# SCH_ECE198-02.net
KiCad netlist of a schematic drawn in EasyEDA
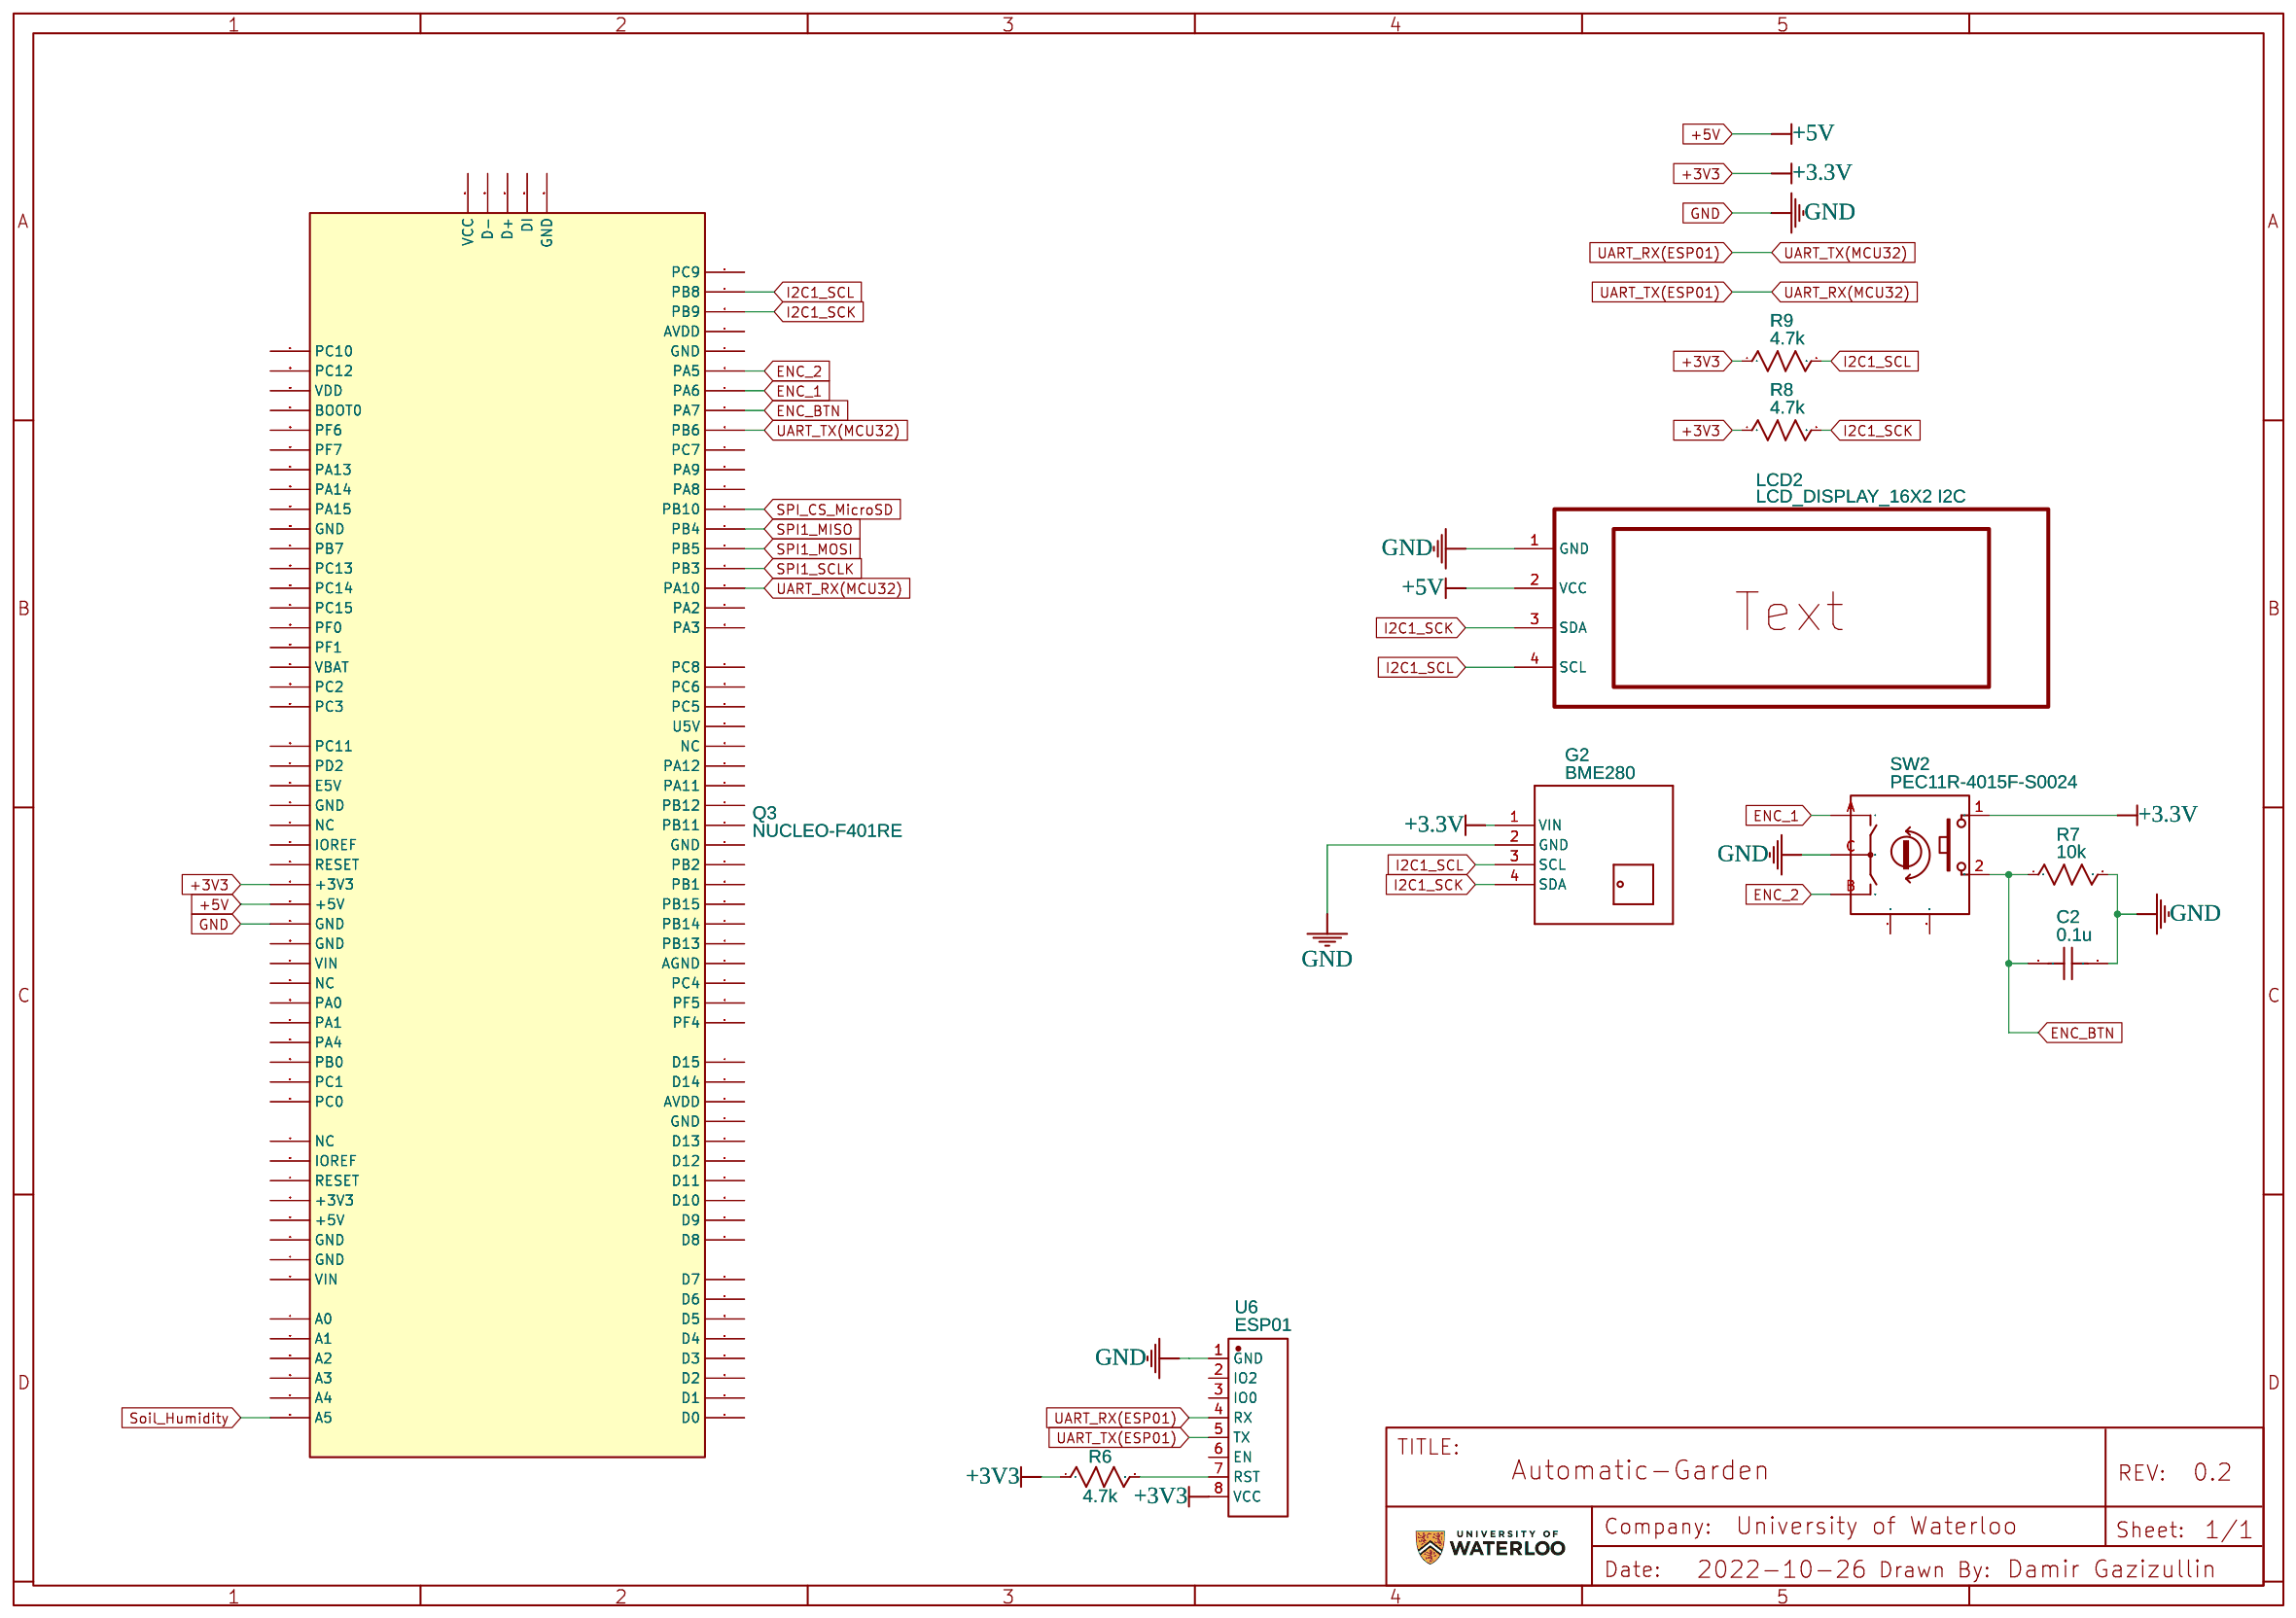
[diagram p0: schematic sheet]

(export (version "E")
  (design (tool "Eeschema 10.0.6"))
  (components
    (comp (ref "C2") (value "0.1u") (libsource (lib "") (part "C_0603_US")))
    (comp (ref "G2") (value "BME280") (libsource (lib "") (part "TEMP-HUM-PRES-BME280")))
    (comp (ref "LCD2") (value "LCD_DISPLAY_16X2 I2C") (libsource (lib "") (part "LCD_DISPLAY_16X2 I2C")))
    (comp (ref "Q3") (value "NUCLEO-F401RE") (libsource (lib "") (part "NUCLEO-F401RE")))
    (comp (ref "R6") (value "4.7k") (libsource (lib "") (part "R_AXIAL-0.5_US")))
    (comp (ref "R7") (value "10k") (libsource (lib "") (part "R_AXIAL-0.5_US")))
    (comp (ref "R8") (value "4.7k") (libsource (lib "") (part "R_0603_US")))
    (comp (ref "R9") (value "4.7k") (libsource (lib "") (part "R_0603_US")))
    (comp (ref "SW2")
      (value "PEC11R-4015F-S0024")
      (fields (field (name "BOM_Supplier Part") "C143789"))
      (libsource (lib "") (part "PEC11R-4015F-S0024"))
    )
    (comp (ref "U6") (value "ESP01") (libsource (lib "") (part "ESP01")))
  )
  (nets
    (net (code "1") (name "+3V3") (class "Default")
      (node (ref "G2") (pin "1") (pinfunction "VIN_1") (pintype "bidirectional"))
      (node (ref "Q3") (pin "91") (pinfunction "+3V3_91") (pintype "unspecified"))
      (node (ref "R6") (pin "1") (pinfunction "1_1") (pintype "unspecified"))
      (node (ref "R8") (pin "1") (pinfunction "1_1") (pintype "unspecified"))
      (node (ref "R9") (pin "1") (pinfunction "1_1") (pintype "unspecified"))
      (node (ref "SW2") (pin "1") (pinfunction "1_1") (pintype "unspecified"))
      (node (ref "U6") (pin "8") (pinfunction "VCC_8") (pintype "unspecified"))
    )
    (net (code "2") (name "+5V") (class "Default")
      (node (ref "LCD2") (pin "2") (pinfunction "VCC_2") (pintype "passive"))
      (node (ref "Q3") (pin "90") (pinfunction "+5V_90") (pintype "unspecified"))
    )
    (net (code "3") (name "ENC_1") (class "Default")
      (node (ref "Q3") (pin "14") (pinfunction "PA6_14") (pintype "bidirectional"))
      (node (ref "SW2") (pin "A") (pinfunction "A_A") (pintype "unspecified"))
    )
    (net (code "4") (name "ENC_2") (class "Default")
      (node (ref "Q3") (pin "13") (pinfunction "PA5_13") (pintype "bidirectional"))
      (node (ref "SW2") (pin "B") (pinfunction "B_B") (pintype "unspecified"))
    )
    (net (code "5") (name "ENC_BTN") (class "Default")
      (node (ref "C2") (pin "1") (pinfunction "1_1") (pintype "unspecified"))
      (node (ref "Q3") (pin "15") (pinfunction "PA7_15") (pintype "bidirectional"))
      (node (ref "R7") (pin "1") (pinfunction "1_1") (pintype "unspecified"))
      (node (ref "SW2") (pin "2") (pinfunction "2_2") (pintype "unspecified"))
    )
    (net (code "6") (name "GND") (class "Default")
      (node (ref "C2") (pin "2") (pinfunction "2_2") (pintype "unspecified"))
      (node (ref "G2") (pin "2") (pinfunction "GND_2") (pintype "bidirectional"))
      (node (ref "LCD2") (pin "1") (pinfunction "GND_1") (pintype "passive"))
      (node (ref "Q3") (pin "89") (pinfunction "GND_89") (pintype "unspecified"))
      (node (ref "R7") (pin "2") (pinfunction "2_2") (pintype "unspecified"))
      (node (ref "SW2") (pin "C") (pinfunction "C_C") (pintype "unspecified"))
      (node (ref "U6") (pin "1") (pinfunction "GND_1") (pintype "unspecified"))
    )
    (net (code "7") (name "I2C1_SCK") (class "Default")
      (node (ref "G2") (pin "4") (pinfunction "SDA_4") (pintype "bidirectional"))
      (node (ref "LCD2") (pin "3") (pinfunction "SDA_3") (pintype "passive"))
      (node (ref "Q3") (pin "10") (pinfunction "PB9_10") (pintype "bidirectional"))
      (node (ref "R8") (pin "2") (pinfunction "2_2") (pintype "unspecified"))
    )
    (net (code "8") (name "I2C1_SCL") (class "Default")
      (node (ref "G2") (pin "3") (pinfunction "SCL_3") (pintype "bidirectional"))
      (node (ref "LCD2") (pin "4") (pinfunction "SCL_4") (pintype "passive"))
      (node (ref "Q3") (pin "9") (pinfunction "PB8_9") (pintype "bidirectional"))
      (node (ref "R9") (pin "2") (pinfunction "2_2") (pintype "unspecified"))
    )
    (net (code "9") (name "Net-(U6-RST)") (class "Default")
      (node (ref "R6") (pin "2") (pinfunction "2_2") (pintype "unspecified"))
      (node (ref "U6") (pin "7") (pinfunction "RST_7") (pintype "unspecified"))
    )
    (net (code "10") (name "SPI1_MISO") (class "Default")
      (node (ref "Q3") (pin "21") (pinfunction "PB4_21") (pintype "bidirectional"))
    )
    (net (code "11") (name "SPI1_MOSI") (class "Default")
      (node (ref "Q3") (pin "22") (pinfunction "PB5_22") (pintype "bidirectional"))
    )
    (net (code "12") (name "SPI1_SCLK") (class "Default")
      (node (ref "Q3") (pin "23") (pinfunction "PB3_23") (pintype "bidirectional"))
    )
    (net (code "13") (name "SPI_CS_MicroSD") (class "Default")
      (node (ref "Q3") (pin "20") (pinfunction "PB10_20") (pintype "bidirectional"))
    )
    (net (code "14") (name "Soil_Humidity") (class "Default")
      (node (ref "Q3") (pin "66") (pinfunction "A5_66") (pintype "unspecified"))
    )
    (net (code "15") (name "UART_RX(ESP01)") (class "Default")
      (node (ref "Q3") (pin "16") (pinfunction "PB6_16") (pintype "bidirectional"))
      (node (ref "U6") (pin "4") (pinfunction "RX_4") (pintype "unspecified"))
    )
    (net (code "16") (name "UART_RX(MCU32)") (class "Default")
      (node (ref "Q3") (pin "24") (pinfunction "PA10_24") (pintype "bidirectional"))
      (node (ref "U6") (pin "5") (pinfunction "TX_5") (pintype "unspecified"))
    )
    (net (code "17") (name "unconnected-(Q3-+3V3-Pad76)") (class "Default")
      (node (ref "Q3") (pin "76") (pinfunction "+3V3_76") (pintype "unspecified"))
    )
    (net (code "18") (name "unconnected-(Q3-+5V-Pad75)") (class "Default")
      (node (ref "Q3") (pin "75") (pinfunction "+5V_75") (pintype "unspecified"))
    )
    (net (code "19") (name "unconnected-(Q3-A0-Pad71)") (class "Default")
      (node (ref "Q3") (pin "71") (pinfunction "A0_71") (pintype "unspecified"))
    )
    (net (code "20") (name "unconnected-(Q3-A1-Pad70)") (class "Default")
      (node (ref "Q3") (pin "70") (pinfunction "A1_70") (pintype "unspecified"))
    )
    (net (code "21") (name "unconnected-(Q3-A2-Pad69)") (class "Default")
      (node (ref "Q3") (pin "69") (pinfunction "A2_69") (pintype "unspecified"))
    )
    (net (code "22") (name "unconnected-(Q3-A3-Pad68)") (class "Default")
      (node (ref "Q3") (pin "68") (pinfunction "A3_68") (pintype "unspecified"))
    )
    (net (code "23") (name "unconnected-(Q3-A4-Pad67)") (class "Default")
      (node (ref "Q3") (pin "67") (pinfunction "A4_67") (pintype "unspecified"))
    )
    (net (code "24") (name "unconnected-(Q3-AGND-Pad43)") (class "Default")
      (node (ref "Q3") (pin "43") (pinfunction "AGND_43") (pintype "unspecified"))
    )
    (net (code "25") (name "unconnected-(Q3-AVDD-Pad11)") (class "Default")
      (node (ref "Q3") (pin "11") (pinfunction "AVDD_11") (pintype "bidirectional"))
    )
    (net (code "26") (name "unconnected-(Q3-AVDD-Pad49)") (class "Default")
      (node (ref "Q3") (pin "49") (pinfunction "AVDD_49") (pintype "unspecified"))
    )
    (net (code "27") (name "unconnected-(Q3-BOOT0-Pad114)") (class "Default")
      (node (ref "Q3") (pin "114") (pinfunction "BOOT0_114") (pintype "unspecified"))
    )
    (net (code "28") (name "unconnected-(Q3-D+-Pad118)") (class "Default")
      (node (ref "Q3") (pin "118") (pinfunction "D+_118") (pintype "unspecified"))
    )
    (net (code "29") (name "unconnected-(Q3-D--Pad118)") (class "Default")
      (node (ref "Q3") (pin "118") (pinfunction "D-_118") (pintype "unspecified"))
    )
    (net (code "30") (name "unconnected-(Q3-D0-Pad65)") (class "Default")
      (node (ref "Q3") (pin "65") (pinfunction "D0_65") (pintype "unspecified"))
    )
    (net (code "31") (name "unconnected-(Q3-D1-Pad64)") (class "Default")
      (node (ref "Q3") (pin "64") (pinfunction "D1_64") (pintype "unspecified"))
    )
    (net (code "32") (name "unconnected-(Q3-D2-Pad63)") (class "Default")
      (node (ref "Q3") (pin "63") (pinfunction "D2_63") (pintype "unspecified"))
    )
    (net (code "33") (name "unconnected-(Q3-D3-Pad62)") (class "Default")
      (node (ref "Q3") (pin "62") (pinfunction "D3_62") (pintype "unspecified"))
    )
    (net (code "34") (name "unconnected-(Q3-D4-Pad61)") (class "Default")
      (node (ref "Q3") (pin "61") (pinfunction "D4_61") (pintype "unspecified"))
    )
    (net (code "35") (name "unconnected-(Q3-D5-Pad60)") (class "Default")
      (node (ref "Q3") (pin "60") (pinfunction "D5_60") (pintype "unspecified"))
    )
    (net (code "36") (name "unconnected-(Q3-D6-Pad59)") (class "Default")
      (node (ref "Q3") (pin "59") (pinfunction "D6_59") (pintype "unspecified"))
    )
    (net (code "37") (name "unconnected-(Q3-D7-Pad58)") (class "Default")
      (node (ref "Q3") (pin "58") (pinfunction "D7_58") (pintype "unspecified"))
    )
    (net (code "38") (name "unconnected-(Q3-D8-Pad56)") (class "Default")
      (node (ref "Q3") (pin "56") (pinfunction "D8_56") (pintype "unspecified"))
    )
    (net (code "39") (name "unconnected-(Q3-D9-Pad55)") (class "Default")
      (node (ref "Q3") (pin "55") (pinfunction "D9_55") (pintype "unspecified"))
    )
    (net (code "40") (name "unconnected-(Q3-D10-Pad54)") (class "Default")
      (node (ref "Q3") (pin "54") (pinfunction "D10_54") (pintype "unspecified"))
    )
    (net (code "41") (name "unconnected-(Q3-D11-Pad53)") (class "Default")
      (node (ref "Q3") (pin "53") (pinfunction "D11_53") (pintype "unspecified"))
    )
    (net (code "42") (name "unconnected-(Q3-D12-Pad52)") (class "Default")
      (node (ref "Q3") (pin "52") (pinfunction "D12_52") (pintype "unspecified"))
    )
    (net (code "43") (name "unconnected-(Q3-D13-Pad51)") (class "Default")
      (node (ref "Q3") (pin "51") (pinfunction "D13_51") (pintype "unspecified"))
    )
    (net (code "44") (name "unconnected-(Q3-D14-Pad48)") (class "Default")
      (node (ref "Q3") (pin "48") (pinfunction "D14_48") (pintype "unspecified"))
    )
    (net (code "45") (name "unconnected-(Q3-D15-Pad47)") (class "Default")
      (node (ref "Q3") (pin "47") (pinfunction "D15_47") (pintype "unspecified"))
    )
    (net (code "46") (name "unconnected-(Q3-DI-Pad118)") (class "Default")
      (node (ref "Q3") (pin "118") (pinfunction "DI_118") (pintype "unspecified"))
    )
    (net (code "47") (name "unconnected-(Q3-E5V-Pad96)") (class "Default")
      (node (ref "Q3") (pin "96") (pinfunction "E5V_96") (pintype "unspecified"))
    )
    (net (code "48") (name "unconnected-(Q3-GND-Pad12)") (class "Default")
      (node (ref "Q3") (pin "12") (pinfunction "GND_12") (pintype "bidirectional"))
    )
    (net (code "49") (name "unconnected-(Q3-GND-Pad37)") (class "Default")
      (node (ref "Q3") (pin "37") (pinfunction "GND_37") (pintype "unspecified"))
    )
    (net (code "50") (name "unconnected-(Q3-GND-Pad50)") (class "Default")
      (node (ref "Q3") (pin "50") (pinfunction "GND_50") (pintype "unspecified"))
    )
    (net (code "51") (name "unconnected-(Q3-GND-Pad73)") (class "Default")
      (node (ref "Q3") (pin "73") (pinfunction "GND_73") (pintype "unspecified"))
    )
    (net (code "52") (name "unconnected-(Q3-GND-Pad74)") (class "Default")
      (node (ref "Q3") (pin "74") (pinfunction "GND_74") (pintype "unspecified"))
    )
    (net (code "53") (name "unconnected-(Q3-GND-Pad88)") (class "Default")
      (node (ref "Q3") (pin "88") (pinfunction "GND_88") (pintype "unspecified"))
    )
    (net (code "54") (name "unconnected-(Q3-GND-Pad95)") (class "Default")
      (node (ref "Q3") (pin "95") (pinfunction "GND_95") (pintype "unspecified"))
    )
    (net (code "55") (name "unconnected-(Q3-GND-Pad108)") (class "Default")
      (node (ref "Q3") (pin "108") (pinfunction "GND_108") (pintype "unspecified"))
    )
    (net (code "56") (name "unconnected-(Q3-GND-Pad118)") (class "Default")
      (node (ref "Q3") (pin "118") (pinfunction "GND_118") (pintype "unspecified"))
    )
    (net (code "57") (name "unconnected-(Q3-IOREF-Pad78)") (class "Default")
      (node (ref "Q3") (pin "78") (pinfunction "IOREF_78") (pintype "unspecified"))
    )
    (net (code "58") (name "unconnected-(Q3-IOREF-Pad93)") (class "Default")
      (node (ref "Q3") (pin "93") (pinfunction "IOREF_93") (pintype "unspecified"))
    )
    (net (code "59") (name "unconnected-(Q3-NC-Pad32)") (class "Default")
      (node (ref "Q3") (pin "32") (pinfunction "NC_32") (pintype "bidirectional"))
    )
    (net (code "60") (name "unconnected-(Q3-NC-Pad79)") (class "Default")
      (node (ref "Q3") (pin "79") (pinfunction "NC_79") (pintype "unspecified"))
    )
    (net (code "61") (name "unconnected-(Q3-NC-Pad86)") (class "Default")
      (node (ref "Q3") (pin "86") (pinfunction "NC_86") (pintype "unspecified"))
    )
    (net (code "62") (name "unconnected-(Q3-NC-Pad94)") (class "Default")
      (node (ref "Q3") (pin "94") (pinfunction "NC_94") (pintype "unspecified"))
    )
    (net (code "63") (name "unconnected-(Q3-PA0-Pad85)") (class "Default")
      (node (ref "Q3") (pin "85") (pinfunction "PA0_85") (pintype "unspecified"))
    )
    (net (code "64") (name "unconnected-(Q3-PA1-Pad84)") (class "Default")
      (node (ref "Q3") (pin "84") (pinfunction "PA1_84") (pintype "unspecified"))
    )
    (net (code "65") (name "unconnected-(Q3-PA2-Pad25)") (class "Default")
      (node (ref "Q3") (pin "25") (pinfunction "PA2_25") (pintype "bidirectional"))
    )
    (net (code "66") (name "unconnected-(Q3-PA3-Pad26)") (class "Default")
      (node (ref "Q3") (pin "26") (pinfunction "PA3_26") (pintype "bidirectional"))
    )
    (net (code "67") (name "unconnected-(Q3-PA4-Pad83)") (class "Default")
      (node (ref "Q3") (pin "83") (pinfunction "PA4_83") (pintype "unspecified"))
    )
    (net (code "68") (name "unconnected-(Q3-PA8-Pad19)") (class "Default")
      (node (ref "Q3") (pin "19") (pinfunction "PA8_19") (pintype "bidirectional"))
    )
    (net (code "69") (name "unconnected-(Q3-PA9-Pad18)") (class "Default")
      (node (ref "Q3") (pin "18") (pinfunction "PA9_18") (pintype "bidirectional"))
    )
    (net (code "70") (name "unconnected-(Q3-PA11-Pad34)") (class "Default")
      (node (ref "Q3") (pin "34") (pinfunction "PA11_34") (pintype "bidirectional"))
    )
    (net (code "71") (name "unconnected-(Q3-PA12-Pad33)") (class "Default")
      (node (ref "Q3") (pin "33") (pinfunction "PA12_33") (pintype "bidirectional"))
    )
    (net (code "72") (name "unconnected-(Q3-PA13-Pad111)") (class "Default")
      (node (ref "Q3") (pin "111") (pinfunction "PA13_111") (pintype "unspecified"))
    )
    (net (code "73") (name "unconnected-(Q3-PA14-Pad110)") (class "Default")
      (node (ref "Q3") (pin "110") (pinfunction "PA14_110") (pintype "unspecified"))
    )
    (net (code "74") (name "unconnected-(Q3-PA15-Pad109)") (class "Default")
      (node (ref "Q3") (pin "109") (pinfunction "PA15_109") (pintype "unspecified"))
    )
    (net (code "75") (name "unconnected-(Q3-PB0-Pad82)") (class "Default")
      (node (ref "Q3") (pin "82") (pinfunction "PB0_82") (pintype "unspecified"))
    )
    (net (code "76") (name "unconnected-(Q3-PB1-Pad39)") (class "Default")
      (node (ref "Q3") (pin "39") (pinfunction "PB1_39") (pintype "unspecified"))
    )
    (net (code "77") (name "unconnected-(Q3-PB2-Pad38)") (class "Default")
      (node (ref "Q3") (pin "38") (pinfunction "PB2_38") (pintype "unspecified"))
    )
    (net (code "78") (name "unconnected-(Q3-PB7-Pad107)") (class "Default")
      (node (ref "Q3") (pin "107") (pinfunction "PB7_107") (pintype "unspecified"))
    )
    (net (code "79") (name "unconnected-(Q3-PB11-Pad36)") (class "Default")
      (node (ref "Q3") (pin "36") (pinfunction "PB11_36") (pintype "unspecified"))
    )
    (net (code "80") (name "unconnected-(Q3-PB12-Pad35)") (class "Default")
      (node (ref "Q3") (pin "35") (pinfunction "PB12_35") (pintype "unspecified"))
    )
    (net (code "81") (name "unconnected-(Q3-PB13-Pad42)") (class "Default")
      (node (ref "Q3") (pin "42") (pinfunction "PB13_42") (pintype "unspecified"))
    )
    (net (code "82") (name "unconnected-(Q3-PB14-Pad41)") (class "Default")
      (node (ref "Q3") (pin "41") (pinfunction "PB14_41") (pintype "unspecified"))
    )
    (net (code "83") (name "unconnected-(Q3-PB15-Pad40)") (class "Default")
      (node (ref "Q3") (pin "40") (pinfunction "PB15_40") (pintype "unspecified"))
    )
    (net (code "84") (name "unconnected-(Q3-PC0-Pad80)") (class "Default")
      (node (ref "Q3") (pin "80") (pinfunction "PC0_80") (pintype "unspecified"))
    )
    (net (code "85") (name "unconnected-(Q3-PC1-Pad81)") (class "Default")
      (node (ref "Q3") (pin "81") (pinfunction "PC1_81") (pintype "unspecified"))
    )
    (net (code "86") (name "unconnected-(Q3-PC2-Pad100)") (class "Default")
      (node (ref "Q3") (pin "100") (pinfunction "PC2_100") (pintype "unspecified"))
    )
    (net (code "87") (name "unconnected-(Q3-PC3-Pad99)") (class "Default")
      (node (ref "Q3") (pin "99") (pinfunction "PC3_99") (pintype "unspecified"))
    )
    (net (code "88") (name "unconnected-(Q3-PC4-Pad44)") (class "Default")
      (node (ref "Q3") (pin "44") (pinfunction "PC4_44") (pintype "unspecified"))
    )
    (net (code "89") (name "unconnected-(Q3-PC5-Pad30)") (class "Default")
      (node (ref "Q3") (pin "30") (pinfunction "PC5_30") (pintype "bidirectional"))
    )
    (net (code "90") (name "unconnected-(Q3-PC6-Pad29)") (class "Default")
      (node (ref "Q3") (pin "29") (pinfunction "PC6_29") (pintype "bidirectional"))
    )
    (net (code "91") (name "unconnected-(Q3-PC7-Pad17)") (class "Default")
      (node (ref "Q3") (pin "17") (pinfunction "PC7_17") (pintype "bidirectional"))
    )
    (net (code "92") (name "unconnected-(Q3-PC8-Pad28)") (class "Default")
      (node (ref "Q3") (pin "28") (pinfunction "PC8_28") (pintype "bidirectional"))
    )
    (net (code "93") (name "unconnected-(Q3-PC9-Pad8)") (class "Default")
      (node (ref "Q3") (pin "8") (pinfunction "PC9_8") (pintype "bidirectional"))
    )
    (net (code "94") (name "unconnected-(Q3-PC10-Pad117)") (class "Default")
      (node (ref "Q3") (pin "117") (pinfunction "PC10_117") (pintype "unspecified"))
    )
    (net (code "95") (name "unconnected-(Q3-PC11-Pad98)") (class "Default")
      (node (ref "Q3") (pin "98") (pinfunction "PC11_98") (pintype "unspecified"))
    )
    (net (code "96") (name "unconnected-(Q3-PC12-Pad116)") (class "Default")
      (node (ref "Q3") (pin "116") (pinfunction "PC12_116") (pintype "unspecified"))
    )
    (net (code "97") (name "unconnected-(Q3-PC13-Pad106)") (class "Default")
      (node (ref "Q3") (pin "106") (pinfunction "PC13_106") (pintype "unspecified"))
    )
    (net (code "98") (name "unconnected-(Q3-PC14-Pad105)") (class "Default")
      (node (ref "Q3") (pin "105") (pinfunction "PC14_105") (pintype "unspecified"))
    )
    (net (code "99") (name "unconnected-(Q3-PC15-Pad104)") (class "Default")
      (node (ref "Q3") (pin "104") (pinfunction "PC15_104") (pintype "unspecified"))
    )
    (net (code "100") (name "unconnected-(Q3-PD2-Pad97)") (class "Default")
      (node (ref "Q3") (pin "97") (pinfunction "PD2_97") (pintype "unspecified"))
    )
    (net (code "101") (name "unconnected-(Q3-PF0-Pad103)") (class "Default")
      (node (ref "Q3") (pin "103") (pinfunction "PF0_103") (pintype "unspecified"))
    )
    (net (code "102") (name "unconnected-(Q3-PF1-Pad102)") (class "Default")
      (node (ref "Q3") (pin "102") (pinfunction "PF1_102") (pintype "unspecified"))
    )
    (net (code "103") (name "unconnected-(Q3-PF4-Pad46)") (class "Default")
      (node (ref "Q3") (pin "46") (pinfunction "PF4_46") (pintype "unspecified"))
    )
    (net (code "104") (name "unconnected-(Q3-PF5-Pad45)") (class "Default")
      (node (ref "Q3") (pin "45") (pinfunction "PF5_45") (pintype "unspecified"))
    )
    (net (code "105") (name "unconnected-(Q3-PF6-Pad113)") (class "Default")
      (node (ref "Q3") (pin "113") (pinfunction "PF6_113") (pintype "unspecified"))
    )
    (net (code "106") (name "unconnected-(Q3-PF7-Pad112)") (class "Default")
      (node (ref "Q3") (pin "112") (pinfunction "PF7_112") (pintype "unspecified"))
    )
    (net (code "107") (name "unconnected-(Q3-RESET-Pad77)") (class "Default")
      (node (ref "Q3") (pin "77") (pinfunction "RESET_77") (pintype "unspecified"))
    )
    (net (code "108") (name "unconnected-(Q3-RESET-Pad92)") (class "Default")
      (node (ref "Q3") (pin "92") (pinfunction "RESET_92") (pintype "unspecified"))
    )
    (net (code "109") (name "unconnected-(Q3-U5V-Pad31)") (class "Default")
      (node (ref "Q3") (pin "31") (pinfunction "U5V_31") (pintype "bidirectional"))
    )
    (net (code "110") (name "unconnected-(Q3-VBAT-Pad101)") (class "Default")
      (node (ref "Q3") (pin "101") (pinfunction "VBAT_101") (pintype "unspecified"))
    )
    (net (code "111") (name "unconnected-(Q3-VCC-Pad118)") (class "Default")
      (node (ref "Q3") (pin "118") (pinfunction "VCC_118") (pintype "unspecified"))
    )
    (net (code "112") (name "unconnected-(Q3-VDD-Pad115)") (class "Default")
      (node (ref "Q3") (pin "115") (pinfunction "VDD_115") (pintype "unspecified"))
    )
    (net (code "113") (name "unconnected-(Q3-VIN-Pad72)") (class "Default")
      (node (ref "Q3") (pin "72") (pinfunction "VIN_72") (pintype "unspecified"))
    )
    (net (code "114") (name "unconnected-(Q3-VIN-Pad87)") (class "Default")
      (node (ref "Q3") (pin "87") (pinfunction "VIN_87") (pintype "unspecified"))
    )
    (net (code "115") (name "unconnected-(SW2-PadMT1)") (class "Default")
      (node (ref "SW2") (pin "MT1") (pinfunction "MT1_MT1") (pintype "unspecified"))
    )
    (net (code "116") (name "unconnected-(SW2-PadMT2)") (class "Default")
      (node (ref "SW2") (pin "MT2") (pinfunction "MT2_MT2") (pintype "unspecified"))
    )
    (net (code "117") (name "unconnected-(U6-EN-Pad6)") (class "Default")
      (node (ref "U6") (pin "6") (pinfunction "EN_6") (pintype "unspecified"))
    )
    (net (code "118") (name "unconnected-(U6-IO0-Pad3)") (class "Default")
      (node (ref "U6") (pin "3") (pinfunction "IO0_3") (pintype "unspecified"))
    )
    (net (code "119") (name "unconnected-(U6-IO2-Pad2)") (class "Default")
      (node (ref "U6") (pin "2") (pinfunction "IO2_2") (pintype "unspecified"))
    )
  )
)
